# ospi151.net
KiCad netlist of a schematic drawn in EAGLE
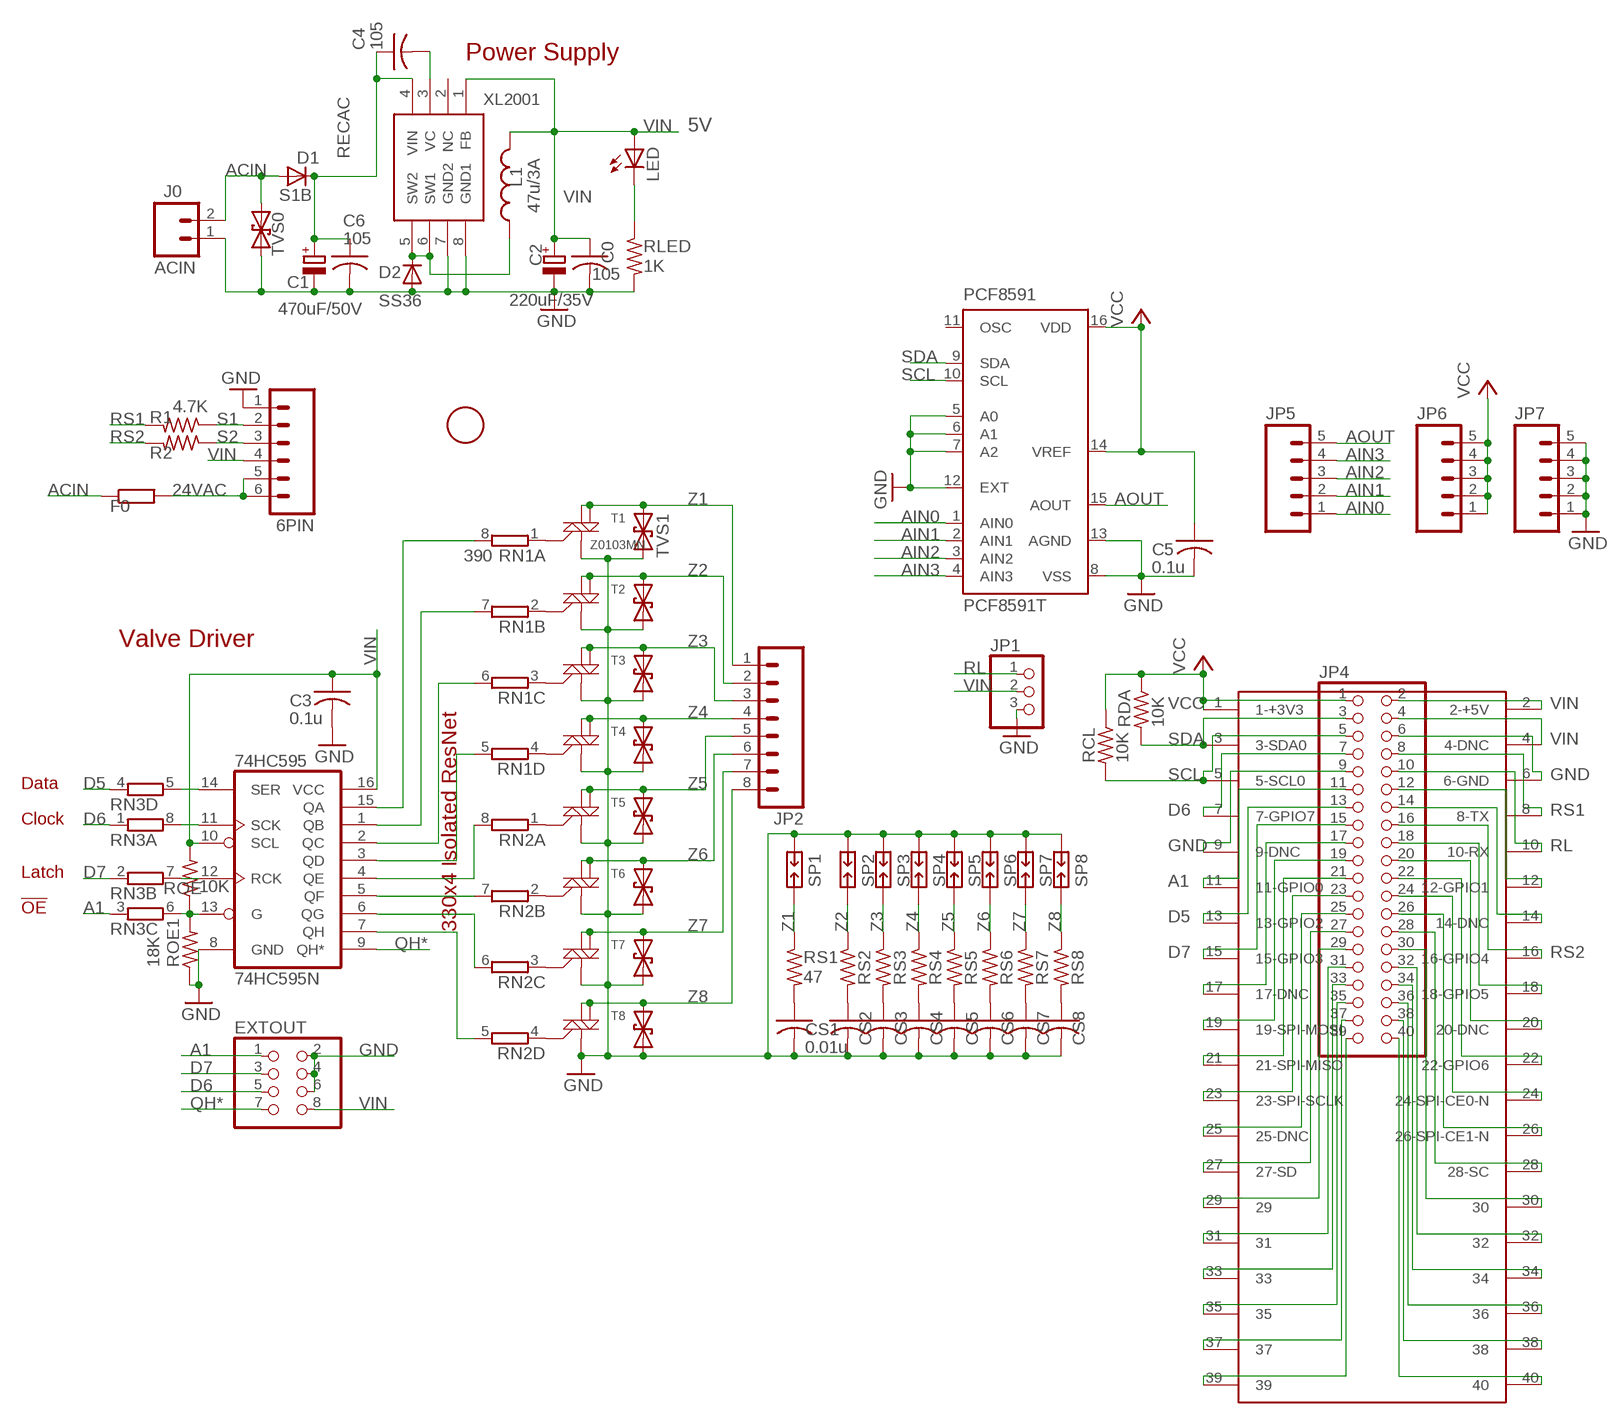
[diagram p0: schematic, sheet 1]

(export (version "E")
  (design (tool "Eeschema 10.0.6"))
  (components
    (comp (ref "1F")
      (value "FIDUCIAL")
      (footprint "eagle-import:FIDUCIAL_1MM")
      (libsource (lib "eagle-import") (part "FIDUCIAL"))
    )
    (comp (ref "6PIN")
      (value "M065MM")
      (footprint "eagle-import:SCREWTERMINAL-5MM-6")
      (libsource (lib "eagle-import") (part "M065MM"))
    )
    (comp (ref "74HC595")
      (value "74HC595N")
      (footprint "eagle-import:SO16")
      (libsource (lib "eagle-import") (part "74595DLS"))
    )
    (comp (ref "C0")
      (value "105")
      (footprint "eagle-import:C0603K")
      (libsource (lib "eagle-import") (part "C-USC0603K"))
    )
    (comp (ref "C1")
      (value "470uF/50V")
      (footprint "eagle-import:E5-10,5")
      (libsource (lib "eagle-import") (part "CPOL-EUE5-10.5"))
    )
    (comp (ref "C2")
      (value "220uF/35V")
      (footprint "eagle-import:E3,5-8")
      (libsource (lib "eagle-import") (part "CPOL-EUE3.5-8"))
    )
    (comp (ref "C3")
      (value "0.1u")
      (footprint "eagle-import:C0603K")
      (libsource (lib "eagle-import") (part "C-USC0603K"))
    )
    (comp (ref "C4")
      (value "105")
      (footprint "eagle-import:C0603K")
      (libsource (lib "eagle-import") (part "C-USC0603K"))
    )
    (comp (ref "C5")
      (value "0.1u")
      (footprint "eagle-import:C0603K")
      (libsource (lib "eagle-import") (part "C-USC0603K"))
    )
    (comp (ref "C6")
      (value "105")
      (footprint "eagle-import:C0603K")
      (libsource (lib "eagle-import") (part "C-USC0603K"))
    )
    (comp (ref "CS1")
      (value "0.01u")
      (footprint "eagle-import:C0603K")
      (libsource (lib "eagle-import") (part "C-USC0603K"))
    )
    (comp (ref "CS2")
      (value "0.01u")
      (footprint "eagle-import:C0603K")
      (libsource (lib "eagle-import") (part "C-USC0603K"))
    )
    (comp (ref "CS3")
      (value "0.01u")
      (footprint "eagle-import:C0603K")
      (libsource (lib "eagle-import") (part "C-USC0603K"))
    )
    (comp (ref "CS4")
      (value "0.01u")
      (footprint "eagle-import:C0603K")
      (libsource (lib "eagle-import") (part "C-USC0603K"))
    )
    (comp (ref "CS5")
      (value "0.01u")
      (footprint "eagle-import:C0603K")
      (libsource (lib "eagle-import") (part "C-USC0603K"))
    )
    (comp (ref "CS6")
      (value "0.01u")
      (footprint "eagle-import:C0603K")
      (libsource (lib "eagle-import") (part "C-USC0603K"))
    )
    (comp (ref "CS7")
      (value "0.01u")
      (footprint "eagle-import:C0603K")
      (libsource (lib "eagle-import") (part "C-USC0603K"))
    )
    (comp (ref "CS8")
      (value "0.01u")
      (footprint "eagle-import:C0603K")
      (libsource (lib "eagle-import") (part "C-USC0603K"))
    )
    (comp (ref "D1")
      (value "S1B")
      (footprint "eagle-import:DO-214AC")
      (libsource (lib "eagle-import") (part "DIODE-DO-214AC"))
    )
    (comp (ref "D2")
      (value "SS36")
      (footprint "eagle-import:SMB")
      (libsource (lib "eagle-import") (part "DIODE-SMB"))
    )
    (comp (ref "EXTOUT")
      (value "PINHD-2X4/90")
      (footprint "eagle-import:2X04_90")
      (libsource (lib "eagle-import") (part "PINHD-2X4/90"))
    )
    (comp (ref "F0")
      (value "R-EU_0207/15")
      (footprint "eagle-import:0207_15")
      (libsource (lib "eagle-import") (part "R-EU_0207/15"))
    )
    (comp (ref "J0")
      (value "ACIN")
      (footprint "eagle-import:SCREWTERMINAL-4MM-2-X")
      (libsource (lib "eagle-import") (part "M024MM-X"))
    )
    (comp (ref "JP1")
      (value "PINHD-1X3")
      (footprint "eagle-import:1X03")
      (libsource (lib "eagle-import") (part "PINHD-1X3"))
    )
    (comp (ref "JP2")
      (value "M085MM-8")
      (footprint "eagle-import:SCREWTERMINAL-5MM-8")
      (libsource (lib "eagle-import") (part "M085MM-8"))
    )
    (comp (ref "JP4")
      (value "PINHD-2X20")
      (footprint "eagle-import:2X20")
      (libsource (lib "eagle-import") (part "PINHD-2X20"))
    )
    (comp (ref "JP5")
      (value "M05PTH")
      (footprint "eagle-import:1X05")
      (libsource (lib "eagle-import") (part "M05PTH"))
    )
    (comp (ref "JP6")
      (value "M05PTH")
      (footprint "eagle-import:1X05")
      (libsource (lib "eagle-import") (part "M05PTH"))
    )
    (comp (ref "JP7")
      (value "M05PTH")
      (footprint "eagle-import:1X05")
      (libsource (lib "eagle-import") (part "M05PTH"))
    )
    (comp (ref "L1")
      (value "47u/3A")
      (footprint "eagle-import:YT1014")
      (libsource (lib "eagle-import") (part "INDUCTORYT1014"))
    )
    (comp (ref "LED")
      (value "LEDCHIPLED_0805")
      (footprint "eagle-import:CHIPLED_0805")
      (libsource (lib "eagle-import") (part "LEDCHIPLED_0805"))
    )
    (comp (ref "PCF8591")
      (value "PCF8591T")
      (footprint "eagle-import:SO16W")
      (fields (field (name "MPN") "PCF8591T/2,512"))
      (libsource (lib "eagle-import") (part "PCF8591T"))
    )
    (comp (ref "R1")
      (value "4.7K")
      (footprint "eagle-import:R0603")
      (libsource (lib "eagle-import") (part "R-US_R0603"))
    )
    (comp (ref "R2")
      (value "4.7K")
      (footprint "eagle-import:R0603")
      (libsource (lib "eagle-import") (part "R-US_R0603"))
    )
    (comp (ref "RCL")
      (value "10K")
      (footprint "eagle-import:R0603")
      (libsource (lib "eagle-import") (part "R-US_R0603"))
    )
    (comp (ref "RDA")
      (value "10K")
      (footprint "eagle-import:R0603")
      (libsource (lib "eagle-import") (part "R-US_R0603"))
    )
    (comp (ref "RLED")
      (value "1K")
      (footprint "eagle-import:R0603")
      (libsource (lib "eagle-import") (part "R-US_R0603"))
    )
    (comp (ref "RN1")
      (value "390")
      (footprint "eagle-import:EXB38V")
      (libsource (lib "eagle-import") (part "4R-NEXB38V"))
    )
    (comp (ref "RN2")
      (value "390")
      (footprint "eagle-import:EXB38V")
      (libsource (lib "eagle-import") (part "4R-NEXB38V"))
    )
    (comp (ref "RN3")
      (value "390")
      (footprint "eagle-import:EXB38V")
      (libsource (lib "eagle-import") (part "4R-NEXB38V"))
    )
    (comp (ref "ROE")
      (value "10K")
      (footprint "eagle-import:R0603")
      (libsource (lib "eagle-import") (part "R-US_R0603"))
    )
    (comp (ref "ROE1")
      (value "18K")
      (footprint "eagle-import:R0603")
      (libsource (lib "eagle-import") (part "R-US_R0603"))
    )
    (comp (ref "RS1")
      (value "47")
      (footprint "eagle-import:R0603")
      (libsource (lib "eagle-import") (part "R-US_R0603"))
    )
    (comp (ref "RS2")
      (value "47")
      (footprint "eagle-import:R0603")
      (libsource (lib "eagle-import") (part "R-US_R0603"))
    )
    (comp (ref "RS3")
      (value "47")
      (footprint "eagle-import:R0603")
      (libsource (lib "eagle-import") (part "R-US_R0603"))
    )
    (comp (ref "RS4")
      (value "47")
      (footprint "eagle-import:R0603")
      (libsource (lib "eagle-import") (part "R-US_R0603"))
    )
    (comp (ref "RS5")
      (value "47")
      (footprint "eagle-import:R0603")
      (libsource (lib "eagle-import") (part "R-US_R0603"))
    )
    (comp (ref "RS6")
      (value "47")
      (footprint "eagle-import:R0603")
      (libsource (lib "eagle-import") (part "R-US_R0603"))
    )
    (comp (ref "RS7")
      (value "47")
      (footprint "eagle-import:R0603")
      (libsource (lib "eagle-import") (part "R-US_R0603"))
    )
    (comp (ref "RS8")
      (value "47")
      (footprint "eagle-import:R0603")
      (libsource (lib "eagle-import") (part "R-US_R0603"))
    )
    (comp (ref "SP1")
      (value "PCB-SGAP")
      (footprint "eagle-import:PCB-SGAP")
      (libsource (lib "eagle-import") (part "PCB-SGAP"))
    )
    (comp (ref "SP2")
      (value "PCB-SGAP")
      (footprint "eagle-import:PCB-SGAP")
      (libsource (lib "eagle-import") (part "PCB-SGAP"))
    )
    (comp (ref "SP3")
      (value "PCB-SGAP")
      (footprint "eagle-import:PCB-SGAP")
      (libsource (lib "eagle-import") (part "PCB-SGAP"))
    )
    (comp (ref "SP4")
      (value "PCB-SGAP")
      (footprint "eagle-import:PCB-SGAP")
      (libsource (lib "eagle-import") (part "PCB-SGAP"))
    )
    (comp (ref "SP5")
      (value "PCB-SGAP")
      (footprint "eagle-import:PCB-SGAP")
      (libsource (lib "eagle-import") (part "PCB-SGAP"))
    )
    (comp (ref "SP6")
      (value "PCB-SGAP")
      (footprint "eagle-import:PCB-SGAP")
      (libsource (lib "eagle-import") (part "PCB-SGAP"))
    )
    (comp (ref "SP7")
      (value "PCB-SGAP")
      (footprint "eagle-import:PCB-SGAP")
      (libsource (lib "eagle-import") (part "PCB-SGAP"))
    )
    (comp (ref "SP8")
      (value "PCB-SGAP")
      (footprint "eagle-import:PCB-SGAP")
      (libsource (lib "eagle-import") (part "PCB-SGAP"))
    )
    (comp (ref "T1")
      (value "Z0103MN")
      (footprint "eagle-import:SOT223")
      (libsource (lib "eagle-import") (part "MAC97SOT223"))
    )
    (comp (ref "T2")
      (value "BT1308W")
      (footprint "eagle-import:SOT223")
      (libsource (lib "eagle-import") (part "MAC97SOT223"))
    )
    (comp (ref "T3")
      (value "BT1308W")
      (footprint "eagle-import:SOT223")
      (libsource (lib "eagle-import") (part "MAC97SOT223"))
    )
    (comp (ref "T4")
      (value "BT1308W")
      (footprint "eagle-import:SOT223")
      (libsource (lib "eagle-import") (part "MAC97SOT223"))
    )
    (comp (ref "T5")
      (value "BT1308W")
      (footprint "eagle-import:SOT223")
      (libsource (lib "eagle-import") (part "MAC97SOT223"))
    )
    (comp (ref "T6")
      (value "BT1308W")
      (footprint "eagle-import:SOT223")
      (libsource (lib "eagle-import") (part "MAC97SOT223"))
    )
    (comp (ref "T7")
      (value "BT1308W")
      (footprint "eagle-import:SOT223")
      (libsource (lib "eagle-import") (part "MAC97SOT223"))
    )
    (comp (ref "T8")
      (value "BT1308W")
      (footprint "eagle-import:SOT223")
      (libsource (lib "eagle-import") (part "MAC97SOT223"))
    )
    (comp (ref "TVS0")
      (value "SMBJ45CA")
      (footprint "eagle-import:SMB")
      (libsource (lib "eagle-import") (part "TVSSMB"))
    )
    (comp (ref "TVS1")
      (value "SMBJ45CA")
      (footprint "eagle-import:SMB")
      (libsource (lib "eagle-import") (part "TVSSMB"))
    )
    (comp (ref "TVS2")
      (value "SMBJ45CA")
      (footprint "eagle-import:SMB")
      (libsource (lib "eagle-import") (part "TVSSMB"))
    )
    (comp (ref "TVS3")
      (value "SMBJ45CA")
      (footprint "eagle-import:SMB")
      (libsource (lib "eagle-import") (part "TVSSMB"))
    )
    (comp (ref "TVS4")
      (value "SMBJ45CA")
      (footprint "eagle-import:SMB")
      (libsource (lib "eagle-import") (part "TVSSMB"))
    )
    (comp (ref "TVS5")
      (value "SMBJ45CA")
      (footprint "eagle-import:SMB")
      (libsource (lib "eagle-import") (part "TVSSMB"))
    )
    (comp (ref "TVS6")
      (value "SMBJ45CA")
      (footprint "eagle-import:SMB")
      (libsource (lib "eagle-import") (part "TVSSMB"))
    )
    (comp (ref "TVS7")
      (value "SMBJ45CA")
      (footprint "eagle-import:SMB")
      (libsource (lib "eagle-import") (part "TVSSMB"))
    )
    (comp (ref "TVS8")
      (value "SMBJ45CA")
      (footprint "eagle-import:SMB")
      (libsource (lib "eagle-import") (part "TVSSMB"))
    )
    (comp (ref "U$2")
      (value "RPIB+B+")
      (footprint "eagle-import:RPIB+")
      (libsource (lib "eagle-import") (part "RPIB+B+"))
    )
    (comp (ref "XL2001")
      (value "XL2011")
      (footprint "eagle-import:SO08")
      (libsource (lib "eagle-import") (part "XL2001"))
    )
  )
  (nets
    (net (code "1") (name "/24VAC") (class "Default")
      (node (ref "6PIN") (pin "5") (pinfunction "5_5") (pintype "passive"))
      (node (ref "6PIN") (pin "6") (pinfunction "6_6") (pintype "passive"))
      (node (ref "F0") (pin "2") (pinfunction "2_2") (pintype "passive"))
    )
    (net (code "2") (name "/A1") (class "Default")
      (node (ref "EXTOUT") (pin "1") (pinfunction "1_1") (pintype "passive"))
      (node (ref "JP4") (pin "11") (pinfunction "11_11") (pintype "passive"))
      (node (ref "RN3") (pin "3") (pinfunction "1_3") (pintype "passive"))
      (node (ref "U$2") (pin "11") (pinfunction "11-GPIO0_11") (pintype "bidirectional"))
    )
    (net (code "3") (name "/ACIN") (class "Default")
      (node (ref "D1") (pin "A") (pinfunction "A_A") (pintype "passive"))
      (node (ref "F0") (pin "1") (pinfunction "1_1") (pintype "passive"))
      (node (ref "J0") (pin "2") (pinfunction "2_2") (pintype "passive"))
      (node (ref "TVS0") (pin "C") (pinfunction "C_C") (pintype "passive"))
    )
    (net (code "4") (name "/AIN0") (class "Default")
      (node (ref "JP5") (pin "1") (pinfunction "1_1") (pintype "passive"))
      (node (ref "PCF8591") (pin "1") (pinfunction "AIN0_1") (pintype "input"))
    )
    (net (code "5") (name "/AIN1") (class "Default")
      (node (ref "JP5") (pin "2") (pinfunction "2_2") (pintype "passive"))
      (node (ref "PCF8591") (pin "2") (pinfunction "AIN1_2") (pintype "input"))
    )
    (net (code "6") (name "/AIN2") (class "Default")
      (node (ref "JP5") (pin "3") (pinfunction "3_3") (pintype "passive"))
      (node (ref "PCF8591") (pin "3") (pinfunction "AIN2_3") (pintype "input"))
    )
    (net (code "7") (name "/AIN3") (class "Default")
      (node (ref "JP5") (pin "4") (pinfunction "4_4") (pintype "passive"))
      (node (ref "PCF8591") (pin "4") (pinfunction "AIN3_4") (pintype "input"))
    )
    (net (code "8") (name "/AOUT") (class "Default")
      (node (ref "JP5") (pin "5") (pinfunction "5_5") (pintype "passive"))
      (node (ref "PCF8591") (pin "15") (pinfunction "AOUT_15") (pintype "output"))
    )
    (net (code "9") (name "/D5") (class "Default")
      (node (ref "JP4") (pin "13") (pinfunction "13_13") (pintype "passive"))
      (node (ref "RN3") (pin "4") (pinfunction "1_4") (pintype "passive"))
      (node (ref "U$2") (pin "13") (pinfunction "13-GPIO2_13") (pintype "bidirectional"))
    )
    (net (code "10") (name "/D6") (class "Default")
      (node (ref "EXTOUT") (pin "5") (pinfunction "5_5") (pintype "passive"))
      (node (ref "JP4") (pin "7") (pinfunction "7_7") (pintype "passive"))
      (node (ref "RN3") (pin "1") (pinfunction "1_1") (pintype "passive"))
      (node (ref "U$2") (pin "7") (pinfunction "7-GPIO7_7") (pintype "bidirectional"))
    )
    (net (code "11") (name "/D7") (class "Default")
      (node (ref "EXTOUT") (pin "3") (pinfunction "3_3") (pintype "passive"))
      (node (ref "JP4") (pin "15") (pinfunction "15_15") (pintype "passive"))
      (node (ref "RN3") (pin "2") (pinfunction "1_2") (pintype "passive"))
      (node (ref "U$2") (pin "15") (pinfunction "15-GPIO3_15") (pintype "bidirectional"))
    )
    (net (code "12") (name "/QH*") (class "Default")
      (node (ref "74HC595") (pin "9") (pinfunction "QH*_9") (pintype "tri_state"))
      (node (ref "EXTOUT") (pin "7") (pinfunction "7_7") (pintype "passive"))
    )
    (net (code "13") (name "/RECAC") (class "Default")
      (node (ref "C1") (pin "+") (pinfunction "+_+") (pintype "passive"))
      (node (ref "C4") (pin "1") (pinfunction "1_1") (pintype "passive"))
      (node (ref "C6") (pin "1") (pinfunction "1_1") (pintype "passive"))
      (node (ref "D1") (pin "C") (pinfunction "C_C") (pintype "passive"))
      (node (ref "XL2001") (pin "4") (pinfunction "VIN_4") (pintype "bidirectional"))
    )
    (net (code "14") (name "/RL") (class "Default")
      (node (ref "JP1") (pin "1") (pinfunction "1_1") (pintype "passive"))
      (node (ref "JP4") (pin "10") (pinfunction "10_10") (pintype "passive"))
      (node (ref "U$2") (pin "10") (pinfunction "10-RX_10") (pintype "bidirectional"))
    )
    (net (code "15") (name "/RS1") (class "Default")
      (node (ref "JP4") (pin "8") (pinfunction "8_8") (pintype "passive"))
      (node (ref "R1") (pin "2") (pinfunction "2_2") (pintype "passive"))
      (node (ref "U$2") (pin "8") (pinfunction "8-TX_8") (pintype "bidirectional"))
    )
    (net (code "16") (name "/RS2") (class "Default")
      (node (ref "JP4") (pin "16") (pinfunction "16_16") (pintype "passive"))
      (node (ref "R2") (pin "2") (pinfunction "2_2") (pintype "passive"))
      (node (ref "U$2") (pin "16") (pinfunction "16-GPIO4_16") (pintype "bidirectional"))
    )
    (net (code "17") (name "/S1") (class "Default")
      (node (ref "6PIN") (pin "2") (pinfunction "2_2") (pintype "passive"))
      (node (ref "R1") (pin "1") (pinfunction "1_1") (pintype "passive"))
    )
    (net (code "18") (name "/S2") (class "Default")
      (node (ref "6PIN") (pin "3") (pinfunction "3_3") (pintype "passive"))
      (node (ref "R2") (pin "1") (pinfunction "1_1") (pintype "passive"))
    )
    (net (code "19") (name "/SCL") (class "Default")
      (node (ref "JP4") (pin "5") (pinfunction "5_5") (pintype "passive"))
      (node (ref "PCF8591") (pin "10") (pinfunction "SCL_10") (pintype "input"))
      (node (ref "RCL") (pin "2") (pinfunction "2_2") (pintype "passive"))
      (node (ref "U$2") (pin "5") (pinfunction "5-SCL0_5") (pintype "bidirectional"))
    )
    (net (code "20") (name "/SDA") (class "Default")
      (node (ref "JP4") (pin "3") (pinfunction "3_3") (pintype "passive"))
      (node (ref "PCF8591") (pin "9") (pinfunction "SDA_9") (pintype "bidirectional"))
      (node (ref "RDA") (pin "2") (pinfunction "2_2") (pintype "passive"))
      (node (ref "U$2") (pin "3") (pinfunction "3-SDA0_3") (pintype "bidirectional"))
    )
    (net (code "21") (name "/VIN") (class "Default")
      (node (ref "6PIN") (pin "4") (pinfunction "4_4") (pintype "passive"))
      (node (ref "74HC595") (pin "10") (pinfunction "SCL_10") (pintype "input"))
      (node (ref "74HC595") (pin "16") (pinfunction "VCC_16") (pintype "power_in"))
      (node (ref "C0") (pin "1") (pinfunction "1_1") (pintype "passive"))
      (node (ref "C2") (pin "+") (pinfunction "+_+") (pintype "passive"))
      (node (ref "C3") (pin "1") (pinfunction "1_1") (pintype "passive"))
      (node (ref "EXTOUT") (pin "8") (pinfunction "8_8") (pintype "passive"))
      (node (ref "JP1") (pin "2") (pinfunction "2_2") (pintype "passive"))
      (node (ref "JP4") (pin "2") (pinfunction "2_2") (pintype "passive"))
      (node (ref "JP4") (pin "4") (pinfunction "4_4") (pintype "passive"))
      (node (ref "L1") (pin "P$2") (pinfunction "2_P$2") (pintype "passive"))
      (node (ref "LED") (pin "A") (pinfunction "A_A") (pintype "passive"))
      (node (ref "ROE") (pin "2") (pinfunction "2_2") (pintype "passive"))
      (node (ref "U$2") (pin "2") (pinfunction "2-+5V_2") (pintype "bidirectional"))
      (node (ref "U$2") (pin "4") (pinfunction "4-DNC_4") (pintype "bidirectional"))
      (node (ref "XL2001") (pin "1") (pinfunction "FB_1") (pintype "input"))
    )
    (net (code "22") (name "/Z1") (class "Default")
      (node (ref "JP2") (pin "1") (pinfunction "1_1") (pintype "passive"))
      (node (ref "RS1") (pin "1") (pinfunction "1_1") (pintype "passive"))
      (node (ref "SP1") (pin "2") (pinfunction "2_2") (pintype "passive"))
      (node (ref "T1") (pin "2") (pinfunction "M2_2") (pintype "bidirectional"))
      (node (ref "T1") (pin "4") (pinfunction "M2-4_4") (pintype "bidirectional"))
      (node (ref "TVS1") (pin "A") (pinfunction "A_A") (pintype "passive"))
    )
    (net (code "23") (name "/Z2") (class "Default")
      (node (ref "JP2") (pin "2") (pinfunction "2_2") (pintype "passive"))
      (node (ref "RS2") (pin "1") (pinfunction "1_1") (pintype "passive"))
      (node (ref "SP2") (pin "2") (pinfunction "2_2") (pintype "passive"))
      (node (ref "T2") (pin "2") (pinfunction "M2_2") (pintype "bidirectional"))
      (node (ref "T2") (pin "4") (pinfunction "M2-4_4") (pintype "bidirectional"))
      (node (ref "TVS2") (pin "A") (pinfunction "A_A") (pintype "passive"))
    )
    (net (code "24") (name "/Z3") (class "Default")
      (node (ref "JP2") (pin "3") (pinfunction "3_3") (pintype "passive"))
      (node (ref "RS3") (pin "1") (pinfunction "1_1") (pintype "passive"))
      (node (ref "SP3") (pin "2") (pinfunction "2_2") (pintype "passive"))
      (node (ref "T3") (pin "2") (pinfunction "M2_2") (pintype "bidirectional"))
      (node (ref "T3") (pin "4") (pinfunction "M2-4_4") (pintype "bidirectional"))
      (node (ref "TVS3") (pin "A") (pinfunction "A_A") (pintype "passive"))
    )
    (net (code "25") (name "/Z4") (class "Default")
      (node (ref "JP2") (pin "4") (pinfunction "4_4") (pintype "passive"))
      (node (ref "RS4") (pin "1") (pinfunction "1_1") (pintype "passive"))
      (node (ref "SP4") (pin "2") (pinfunction "2_2") (pintype "passive"))
      (node (ref "T4") (pin "2") (pinfunction "M2_2") (pintype "bidirectional"))
      (node (ref "T4") (pin "4") (pinfunction "M2-4_4") (pintype "bidirectional"))
      (node (ref "TVS4") (pin "A") (pinfunction "A_A") (pintype "passive"))
    )
    (net (code "26") (name "/Z5") (class "Default")
      (node (ref "JP2") (pin "5") (pinfunction "5_5") (pintype "passive"))
      (node (ref "RS5") (pin "1") (pinfunction "1_1") (pintype "passive"))
      (node (ref "SP5") (pin "2") (pinfunction "2_2") (pintype "passive"))
      (node (ref "T5") (pin "2") (pinfunction "M2_2") (pintype "bidirectional"))
      (node (ref "T5") (pin "4") (pinfunction "M2-4_4") (pintype "bidirectional"))
      (node (ref "TVS5") (pin "A") (pinfunction "A_A") (pintype "passive"))
    )
    (net (code "27") (name "/Z6") (class "Default")
      (node (ref "JP2") (pin "6") (pinfunction "6_6") (pintype "passive"))
      (node (ref "RS6") (pin "1") (pinfunction "1_1") (pintype "passive"))
      (node (ref "SP6") (pin "2") (pinfunction "2_2") (pintype "passive"))
      (node (ref "T6") (pin "2") (pinfunction "M2_2") (pintype "bidirectional"))
      (node (ref "T6") (pin "4") (pinfunction "M2-4_4") (pintype "bidirectional"))
      (node (ref "TVS6") (pin "A") (pinfunction "A_A") (pintype "passive"))
    )
    (net (code "28") (name "/Z7") (class "Default")
      (node (ref "JP2") (pin "7") (pinfunction "7_7") (pintype "passive"))
      (node (ref "RS7") (pin "1") (pinfunction "1_1") (pintype "passive"))
      (node (ref "SP7") (pin "2") (pinfunction "2_2") (pintype "passive"))
      (node (ref "T7") (pin "2") (pinfunction "M2_2") (pintype "bidirectional"))
      (node (ref "T7") (pin "4") (pinfunction "M2-4_4") (pintype "bidirectional"))
      (node (ref "TVS7") (pin "A") (pinfunction "A_A") (pintype "passive"))
    )
    (net (code "29") (name "/Z8") (class "Default")
      (node (ref "JP2") (pin "8") (pinfunction "8_8") (pintype "passive"))
      (node (ref "RS8") (pin "1") (pinfunction "1_1") (pintype "passive"))
      (node (ref "SP8") (pin "2") (pinfunction "2_2") (pintype "passive"))
      (node (ref "T8") (pin "2") (pinfunction "M2_2") (pintype "bidirectional"))
      (node (ref "T8") (pin "4") (pinfunction "M2-4_4") (pintype "bidirectional"))
      (node (ref "TVS8") (pin "A") (pinfunction "A_A") (pintype "passive"))
    )
    (net (code "30") (name "GND") (class "Default")
      (node (ref "6PIN") (pin "1") (pinfunction "1_1") (pintype "passive"))
      (node (ref "74HC595") (pin "8") (pinfunction "GND_8") (pintype "power_in"))
      (node (ref "C0") (pin "2") (pinfunction "2_2") (pintype "passive"))
      (node (ref "C1") (pin "-") (pinfunction "-_-") (pintype "passive"))
      (node (ref "C2") (pin "-") (pinfunction "-_-") (pintype "passive"))
      (node (ref "C3") (pin "2") (pinfunction "2_2") (pintype "passive"))
      (node (ref "C5") (pin "2") (pinfunction "2_2") (pintype "passive"))
      (node (ref "C6") (pin "2") (pinfunction "2_2") (pintype "passive"))
      (node (ref "CS1") (pin "2") (pinfunction "2_2") (pintype "passive"))
      (node (ref "CS2") (pin "2") (pinfunction "2_2") (pintype "passive"))
      (node (ref "CS3") (pin "2") (pinfunction "2_2") (pintype "passive"))
      (node (ref "CS4") (pin "2") (pinfunction "2_2") (pintype "passive"))
      (node (ref "CS5") (pin "2") (pinfunction "2_2") (pintype "passive"))
      (node (ref "CS6") (pin "2") (pinfunction "2_2") (pintype "passive"))
      (node (ref "CS7") (pin "2") (pinfunction "2_2") (pintype "passive"))
      (node (ref "CS8") (pin "2") (pinfunction "2_2") (pintype "passive"))
      (node (ref "D2") (pin "A") (pinfunction "A_A") (pintype "passive"))
      (node (ref "EXTOUT") (pin "2") (pinfunction "2_2") (pintype "passive"))
      (node (ref "EXTOUT") (pin "4") (pinfunction "4_4") (pintype "passive"))
      (node (ref "EXTOUT") (pin "6") (pinfunction "6_6") (pintype "passive"))
      (node (ref "J0") (pin "1") (pinfunction "1_1") (pintype "passive"))
      (node (ref "JP1") (pin "3") (pinfunction "3_3") (pintype "passive"))
      (node (ref "JP4") (pin "6") (pinfunction "6_6") (pintype "passive"))
      (node (ref "JP4") (pin "9") (pinfunction "9_9") (pintype "passive"))
      (node (ref "JP7") (pin "1") (pinfunction "1_1") (pintype "passive"))
      (node (ref "JP7") (pin "2") (pinfunction "2_2") (pintype "passive"))
      (node (ref "JP7") (pin "3") (pinfunction "3_3") (pintype "passive"))
      (node (ref "JP7") (pin "4") (pinfunction "4_4") (pintype "passive"))
      (node (ref "JP7") (pin "5") (pinfunction "5_5") (pintype "passive"))
      (node (ref "PCF8591") (pin "12") (pinfunction "EXT_12") (pintype "input"))
      (node (ref "PCF8591") (pin "13") (pinfunction "AGND_13") (pintype "power_in"))
      (node (ref "PCF8591") (pin "5") (pinfunction "A0_5") (pintype "input"))
      (node (ref "PCF8591") (pin "6") (pinfunction "A1_6") (pintype "input"))
      (node (ref "PCF8591") (pin "7") (pinfunction "A2_7") (pintype "input"))
      (node (ref "PCF8591") (pin "8") (pinfunction "VSS_8") (pintype "power_in"))
      (node (ref "RLED") (pin "2") (pinfunction "2_2") (pintype "passive"))
      (node (ref "ROE1") (pin "1") (pinfunction "1_1") (pintype "passive"))
      (node (ref "SP1") (pin "1") (pinfunction "1_1") (pintype "passive"))
      (node (ref "SP2") (pin "1") (pinfunction "1_1") (pintype "passive"))
      (node (ref "SP3") (pin "1") (pinfunction "1_1") (pintype "passive"))
      (node (ref "SP4") (pin "1") (pinfunction "1_1") (pintype "passive"))
      (node (ref "SP5") (pin "1") (pinfunction "1_1") (pintype "passive"))
      (node (ref "SP6") (pin "1") (pinfunction "1_1") (pintype "passive"))
      (node (ref "SP7") (pin "1") (pinfunction "1_1") (pintype "passive"))
      (node (ref "SP8") (pin "1") (pinfunction "1_1") (pintype "passive"))
      (node (ref "T1") (pin "1") (pinfunction "M1_1") (pintype "bidirectional"))
      (node (ref "T2") (pin "1") (pinfunction "M1_1") (pintype "bidirectional"))
      (node (ref "T3") (pin "1") (pinfunction "M1_1") (pintype "bidirectional"))
      (node (ref "T4") (pin "1") (pinfunction "M1_1") (pintype "bidirectional"))
      (node (ref "T5") (pin "1") (pinfunction "M1_1") (pintype "bidirectional"))
      (node (ref "T6") (pin "1") (pinfunction "M1_1") (pintype "bidirectional"))
      (node (ref "T7") (pin "1") (pinfunction "M1_1") (pintype "bidirectional"))
      (node (ref "T8") (pin "1") (pinfunction "M1_1") (pintype "bidirectional"))
      (node (ref "TVS0") (pin "A") (pinfunction "A_A") (pintype "passive"))
      (node (ref "TVS1") (pin "C") (pinfunction "C_C") (pintype "passive"))
      (node (ref "TVS2") (pin "C") (pinfunction "C_C") (pintype "passive"))
      (node (ref "TVS3") (pin "C") (pinfunction "C_C") (pintype "passive"))
      (node (ref "TVS4") (pin "C") (pinfunction "C_C") (pintype "passive"))
      (node (ref "TVS5") (pin "C") (pinfunction "C_C") (pintype "passive"))
      (node (ref "TVS6") (pin "C") (pinfunction "C_C") (pintype "passive"))
      (node (ref "TVS7") (pin "C") (pinfunction "C_C") (pintype "passive"))
      (node (ref "TVS8") (pin "C") (pinfunction "C_C") (pintype "passive"))
      (node (ref "U$2") (pin "6") (pinfunction "6-GND_6") (pintype "bidirectional"))
      (node (ref "U$2") (pin "9") (pinfunction "9-DNC_9") (pintype "bidirectional"))
      (node (ref "XL2001") (pin "7") (pinfunction "GND2_7") (pintype "power_in"))
      (node (ref "XL2001") (pin "8") (pinfunction "GND1_8") (pintype "power_in"))
    )
    (net (code "31") (name "Net-(74HC595-G)") (class "Default")
      (node (ref "74HC595") (pin "13") (pinfunction "G_13") (pintype "input"))
      (node (ref "RN3") (pin "6") (pinfunction "2_6") (pintype "passive"))
      (node (ref "ROE") (pin "1") (pinfunction "1_1") (pintype "passive"))
      (node (ref "ROE1") (pin "2") (pinfunction "2_2") (pintype "passive"))
    )
    (net (code "32") (name "Net-(74HC595-QA)") (class "Default")
      (node (ref "74HC595") (pin "15") (pinfunction "QA_15") (pintype "tri_state"))
      (node (ref "RN1") (pin "8") (pinfunction "2_8") (pintype "passive"))
    )
    (net (code "33") (name "Net-(74HC595-QB)") (class "Default")
      (node (ref "74HC595") (pin "1") (pinfunction "QB_1") (pintype "tri_state"))
      (node (ref "RN1") (pin "7") (pinfunction "2_7") (pintype "passive"))
    )
    (net (code "34") (name "Net-(74HC595-QC)") (class "Default")
      (node (ref "74HC595") (pin "2") (pinfunction "QC_2") (pintype "tri_state"))
      (node (ref "RN1") (pin "6") (pinfunction "2_6") (pintype "passive"))
    )
    (net (code "35") (name "Net-(74HC595-QD)") (class "Default")
      (node (ref "74HC595") (pin "3") (pinfunction "QD_3") (pintype "tri_state"))
      (node (ref "RN1") (pin "5") (pinfunction "2_5") (pintype "passive"))
    )
    (net (code "36") (name "Net-(74HC595-QE)") (class "Default")
      (node (ref "74HC595") (pin "4") (pinfunction "QE_4") (pintype "tri_state"))
      (node (ref "RN2") (pin "8") (pinfunction "2_8") (pintype "passive"))
    )
    (net (code "37") (name "Net-(74HC595-QF)") (class "Default")
      (node (ref "74HC595") (pin "5") (pinfunction "QF_5") (pintype "tri_state"))
      (node (ref "RN2") (pin "7") (pinfunction "2_7") (pintype "passive"))
    )
    (net (code "38") (name "Net-(74HC595-QG)") (class "Default")
      (node (ref "74HC595") (pin "6") (pinfunction "QG_6") (pintype "tri_state"))
      (node (ref "RN2") (pin "6") (pinfunction "2_6") (pintype "passive"))
    )
    (net (code "39") (name "Net-(74HC595-QH)") (class "Default")
      (node (ref "74HC595") (pin "7") (pinfunction "QH_7") (pintype "tri_state"))
      (node (ref "RN2") (pin "5") (pinfunction "2_5") (pintype "passive"))
    )
    (net (code "40") (name "Net-(74HC595-RCK)") (class "Default")
      (node (ref "74HC595") (pin "12") (pinfunction "RCK_12") (pintype "input"))
      (node (ref "RN3") (pin "7") (pinfunction "2_7") (pintype "passive"))
    )
    (net (code "41") (name "Net-(74HC595-SCK)") (class "Default")
      (node (ref "74HC595") (pin "11") (pinfunction "SCK_11") (pintype "input"))
      (node (ref "RN3") (pin "8") (pinfunction "2_8") (pintype "passive"))
    )
    (net (code "42") (name "Net-(74HC595-SER)") (class "Default")
      (node (ref "74HC595") (pin "14") (pinfunction "SER_14") (pintype "input"))
      (node (ref "RN3") (pin "5") (pinfunction "2_5") (pintype "passive"))
    )
    (net (code "43") (name "Net-(CS1-Pad1)") (class "Default")
      (node (ref "CS1") (pin "1") (pinfunction "1_1") (pintype "passive"))
      (node (ref "RS1") (pin "2") (pinfunction "2_2") (pintype "passive"))
    )
    (net (code "44") (name "Net-(CS2-Pad1)") (class "Default")
      (node (ref "CS2") (pin "1") (pinfunction "1_1") (pintype "passive"))
      (node (ref "RS2") (pin "2") (pinfunction "2_2") (pintype "passive"))
    )
    (net (code "45") (name "Net-(CS3-Pad1)") (class "Default")
      (node (ref "CS3") (pin "1") (pinfunction "1_1") (pintype "passive"))
      (node (ref "RS3") (pin "2") (pinfunction "2_2") (pintype "passive"))
    )
    (net (code "46") (name "Net-(CS4-Pad1)") (class "Default")
      (node (ref "CS4") (pin "1") (pinfunction "1_1") (pintype "passive"))
      (node (ref "RS4") (pin "2") (pinfunction "2_2") (pintype "passive"))
    )
    (net (code "47") (name "Net-(CS5-Pad1)") (class "Default")
      (node (ref "CS5") (pin "1") (pinfunction "1_1") (pintype "passive"))
      (node (ref "RS5") (pin "2") (pinfunction "2_2") (pintype "passive"))
    )
    (net (code "48") (name "Net-(CS6-Pad1)") (class "Default")
      (node (ref "CS6") (pin "1") (pinfunction "1_1") (pintype "passive"))
      (node (ref "RS6") (pin "2") (pinfunction "2_2") (pintype "passive"))
    )
    (net (code "49") (name "Net-(CS7-Pad1)") (class "Default")
      (node (ref "CS7") (pin "1") (pinfunction "1_1") (pintype "passive"))
      (node (ref "RS7") (pin "2") (pinfunction "2_2") (pintype "passive"))
    )
    (net (code "50") (name "Net-(CS8-Pad1)") (class "Default")
      (node (ref "CS8") (pin "1") (pinfunction "1_1") (pintype "passive"))
      (node (ref "RS8") (pin "2") (pinfunction "2_2") (pintype "passive"))
    )
    (net (code "51") (name "Net-(JP4-Pad29)") (class "Default")
      (node (ref "JP4") (pin "29") (pinfunction "29_29") (pintype "passive"))
      (node (ref "U$2") (pin "29") (pinfunction "29_29") (pintype "bidirectional"))
    )
    (net (code "52") (name "Net-(JP4-Pad30)") (class "Default")
      (node (ref "JP4") (pin "30") (pinfunction "30_30") (pintype "passive"))
      (node (ref "U$2") (pin "30") (pinfunction "30_30") (pintype "bidirectional"))
    )
    (net (code "53") (name "Net-(JP4-Pad31)") (class "Default")
      (node (ref "JP4") (pin "31") (pinfunction "31_31") (pintype "passive"))
      (node (ref "U$2") (pin "31") (pinfunction "31_31") (pintype "bidirectional"))
    )
    (net (code "54") (name "Net-(JP4-Pad32)") (class "Default")
      (node (ref "JP4") (pin "32") (pinfunction "32_32") (pintype "passive"))
      (node (ref "U$2") (pin "32") (pinfunction "32_32") (pintype "bidirectional"))
    )
    (net (code "55") (name "Net-(JP4-Pad33)") (class "Default")
      (node (ref "JP4") (pin "33") (pinfunction "33_33") (pintype "passive"))
      (node (ref "U$2") (pin "33") (pinfunction "33_33") (pintype "bidirectional"))
    )
    (net (code "56") (name "Net-(JP4-Pad34)") (class "Default")
      (node (ref "JP4") (pin "34") (pinfunction "34_34") (pintype "passive"))
      (node (ref "U$2") (pin "34") (pinfunction "34_34") (pintype "bidirectional"))
    )
    (net (code "57") (name "Net-(JP4-Pad35)") (class "Default")
      (node (ref "JP4") (pin "35") (pinfunction "35_35") (pintype "passive"))
      (node (ref "U$2") (pin "35") (pinfunction "35_35") (pintype "bidirectional"))
    )
    (net (code "58") (name "Net-(JP4-Pad36)") (class "Default")
      (node (ref "JP4") (pin "36") (pinfunction "36_36") (pintype "passive"))
      (node (ref "U$2") (pin "36") (pinfunction "36_36") (pintype "bidirectional"))
    )
    (net (code "59") (name "Net-(JP4-Pad37)") (class "Default")
      (node (ref "JP4") (pin "37") (pinfunction "37_37") (pintype "passive"))
      (node (ref "U$2") (pin "37") (pinfunction "37_37") (pintype "bidirectional"))
    )
    (net (code "60") (name "Net-(JP4-Pad38)") (class "Default")
      (node (ref "JP4") (pin "38") (pinfunction "38_38") (pintype "passive"))
      (node (ref "U$2") (pin "38") (pinfunction "38_38") (pintype "bidirectional"))
    )
    (net (code "61") (name "Net-(JP4-Pad39)") (class "Default")
      (node (ref "JP4") (pin "39") (pinfunction "39_39") (pintype "passive"))
      (node (ref "U$2") (pin "39") (pinfunction "39_39") (pintype "bidirectional"))
    )
    (net (code "62") (name "Net-(JP4-Pad40)") (class "Default")
      (node (ref "JP4") (pin "40") (pinfunction "40_40") (pintype "passive"))
      (node (ref "U$2") (pin "40") (pinfunction "40_40") (pintype "bidirectional"))
    )
    (net (code "63") (name "Net-(L1-1)") (class "Default")
      (node (ref "D2") (pin "C") (pinfunction "C_C") (pintype "passive"))
      (node (ref "L1") (pin "P$1") (pinfunction "1_P$1") (pintype "passive"))
      (node (ref "XL2001") (pin "5") (pinfunction "SW2_5") (pintype "power_in"))
      (node (ref "XL2001") (pin "6") (pinfunction "SW1_6") (pintype "power_in"))
    )
    (net (code "64") (name "Net-(LED-PadC)") (class "Default")
      (node (ref "LED") (pin "C") (pinfunction "C_C") (pintype "passive"))
      (node (ref "RLED") (pin "1") (pinfunction "1_1") (pintype "passive"))
    )
    (net (code "65") (name "Net-(RN1B-1)") (class "Default")
      (node (ref "RN1") (pin "2") (pinfunction "1_2") (pintype "passive"))
      (node (ref "T2") (pin "3") (pinfunction "G_3") (pintype "bidirectional"))
    )
    (net (code "66") (name "Net-(RN1C-1)") (class "Default")
      (node (ref "RN1") (pin "3") (pinfunction "1_3") (pintype "passive"))
      (node (ref "T3") (pin "3") (pinfunction "G_3") (pintype "bidirectional"))
    )
    (net (code "67") (name "Net-(RN1D-1)") (class "Default")
      (node (ref "RN1") (pin "4") (pinfunction "1_4") (pintype "passive"))
      (node (ref "T4") (pin "3") (pinfunction "G_3") (pintype "bidirectional"))
    )
    (net (code "68") (name "Net-(RN2B-1)") (class "Default")
      (node (ref "RN2") (pin "2") (pinfunction "1_2") (pintype "passive"))
      (node (ref "T6") (pin "3") (pinfunction "G_3") (pintype "bidirectional"))
    )
    (net (code "69") (name "Net-(RN2C-1)") (class "Default")
      (node (ref "RN2") (pin "3") (pinfunction "1_3") (pintype "passive"))
      (node (ref "T7") (pin "3") (pinfunction "G_3") (pintype "bidirectional"))
    )
    (net (code "70") (name "Net-(RN2D-1)") (class "Default")
      (node (ref "RN2") (pin "4") (pinfunction "1_4") (pintype "passive"))
      (node (ref "T8") (pin "3") (pinfunction "G_3") (pintype "bidirectional"))
    )
    (net (code "71") (name "Net-(T1-G)") (class "Default")
      (node (ref "RN1") (pin "1") (pinfunction "1_1") (pintype "passive"))
      (node (ref "T1") (pin "3") (pinfunction "G_3") (pintype "bidirectional"))
    )
    (net (code "72") (name "Net-(T5-G)") (class "Default")
      (node (ref "RN2") (pin "1") (pinfunction "1_1") (pintype "passive"))
      (node (ref "T5") (pin "3") (pinfunction "G_3") (pintype "bidirectional"))
    )
    (net (code "73") (name "Net-(U$2-12-GPIO1)") (class "Default")
      (node (ref "JP4") (pin "12") (pinfunction "12_12") (pintype "passive"))
      (node (ref "U$2") (pin "12") (pinfunction "12-GPIO1_12") (pintype "bidirectional"))
    )
    (net (code "74") (name "Net-(U$2-14-DNC)") (class "Default")
      (node (ref "JP4") (pin "14") (pinfunction "14_14") (pintype "passive"))
      (node (ref "U$2") (pin "14") (pinfunction "14-DNC_14") (pintype "bidirectional"))
    )
    (net (code "75") (name "Net-(U$2-17-DNC)") (class "Default")
      (node (ref "JP4") (pin "17") (pinfunction "17_17") (pintype "passive"))
      (node (ref "U$2") (pin "17") (pinfunction "17-DNC_17") (pintype "bidirectional"))
    )
    (net (code "76") (name "Net-(U$2-18-GPIO5)") (class "Default")
      (node (ref "JP4") (pin "18") (pinfunction "18_18") (pintype "passive"))
      (node (ref "U$2") (pin "18") (pinfunction "18-GPIO5_18") (pintype "bidirectional"))
    )
    (net (code "77") (name "Net-(U$2-19-SPI-MOSI)") (class "Default")
      (node (ref "JP4") (pin "19") (pinfunction "19_19") (pintype "passive"))
      (node (ref "U$2") (pin "19") (pinfunction "19-SPI-MOSI_19") (pintype "bidirectional"))
    )
    (net (code "78") (name "Net-(U$2-20-DNC)") (class "Default")
      (node (ref "JP4") (pin "20") (pinfunction "20_20") (pintype "passive"))
      (node (ref "U$2") (pin "20") (pinfunction "20-DNC_20") (pintype "bidirectional"))
    )
    (net (code "79") (name "Net-(U$2-21-SPI-MISO)") (class "Default")
      (node (ref "JP4") (pin "21") (pinfunction "21_21") (pintype "passive"))
      (node (ref "U$2") (pin "21") (pinfunction "21-SPI-MISO_21") (pintype "bidirectional"))
    )
    (net (code "80") (name "Net-(U$2-22-GPIO6)") (class "Default")
      (node (ref "JP4") (pin "22") (pinfunction "22_22") (pintype "passive"))
      (node (ref "U$2") (pin "22") (pinfunction "22-GPIO6_22") (pintype "bidirectional"))
    )
    (net (code "81") (name "Net-(U$2-23-SPI-SCLK)") (class "Default")
      (node (ref "JP4") (pin "23") (pinfunction "23_23") (pintype "passive"))
      (node (ref "U$2") (pin "23") (pinfunction "23-SPI-SCLK_23") (pintype "bidirectional"))
    )
    (net (code "82") (name "Net-(U$2-24-SPI-CE0-N)") (class "Default")
      (node (ref "JP4") (pin "24") (pinfunction "24_24") (pintype "passive"))
      (node (ref "U$2") (pin "24") (pinfunction "24-SPI-CE0-N_24") (pintype "bidirectional"))
    )
    (net (code "83") (name "Net-(U$2-25-DNC)") (class "Default")
      (node (ref "JP4") (pin "25") (pinfunction "25_25") (pintype "passive"))
      (node (ref "U$2") (pin "25") (pinfunction "25-DNC_25") (pintype "bidirectional"))
    )
    (net (code "84") (name "Net-(U$2-26-SPI-CE1-N)") (class "Default")
      (node (ref "JP4") (pin "26") (pinfunction "26_26") (pintype "passive"))
      (node (ref "U$2") (pin "26") (pinfunction "26-SPI-CE1-N_26") (pintype "bidirectional"))
    )
    (net (code "85") (name "Net-(U$2-27-SD)") (class "Default")
      (node (ref "JP4") (pin "27") (pinfunction "27_27") (pintype "passive"))
      (node (ref "U$2") (pin "27") (pinfunction "27-SD_27") (pintype "bidirectional"))
    )
    (net (code "86") (name "Net-(U$2-28-SC)") (class "Default")
      (node (ref "JP4") (pin "28") (pinfunction "28_28") (pintype "passive"))
      (node (ref "U$2") (pin "28") (pinfunction "28-SC_28") (pintype "bidirectional"))
    )
    (net (code "87") (name "Net-(XL2001-VC)") (class "Default")
      (node (ref "C4") (pin "2") (pinfunction "2_2") (pintype "passive"))
      (node (ref "XL2001") (pin "3") (pinfunction "VC_3") (pintype "input"))
    )
    (net (code "88") (name "VCC") (class "Default")
      (node (ref "C5") (pin "1") (pinfunction "1_1") (pintype "passive"))
      (node (ref "JP4") (pin "1") (pinfunction "1_1") (pintype "passive"))
      (node (ref "JP6") (pin "1") (pinfunction "1_1") (pintype "passive"))
      (node (ref "JP6") (pin "2") (pinfunction "2_2") (pintype "passive"))
      (node (ref "JP6") (pin "3") (pinfunction "3_3") (pintype "passive"))
      (node (ref "JP6") (pin "4") (pinfunction "4_4") (pintype "passive"))
      (node (ref "JP6") (pin "5") (pinfunction "5_5") (pintype "passive"))
      (node (ref "PCF8591") (pin "14") (pinfunction "VREF_14") (pintype "input"))
      (node (ref "PCF8591") (pin "16") (pinfunction "VDD_16") (pintype "power_in"))
      (node (ref "RCL") (pin "1") (pinfunction "1_1") (pintype "passive"))
      (node (ref "RDA") (pin "1") (pinfunction "1_1") (pintype "passive"))
      (node (ref "U$2") (pin "1") (pinfunction "1-+3V3_1") (pintype "bidirectional"))
    )
    (net (code "89") (name "unconnected-(PCF8591-OSC-Pad11)") (class "Default")
      (node (ref "PCF8591") (pin "11") (pinfunction "OSC_11") (pintype "input"))
    )
    (net (code "90") (name "unconnected-(XL2001-NC-Pad2)") (class "Default")
      (node (ref "XL2001") (pin "2") (pinfunction "NC_2") (pintype "input"))
    )
  )
)
